# Main_oak_cm4_16.net
KiCad netlist of a schematic drawn in EAGLE
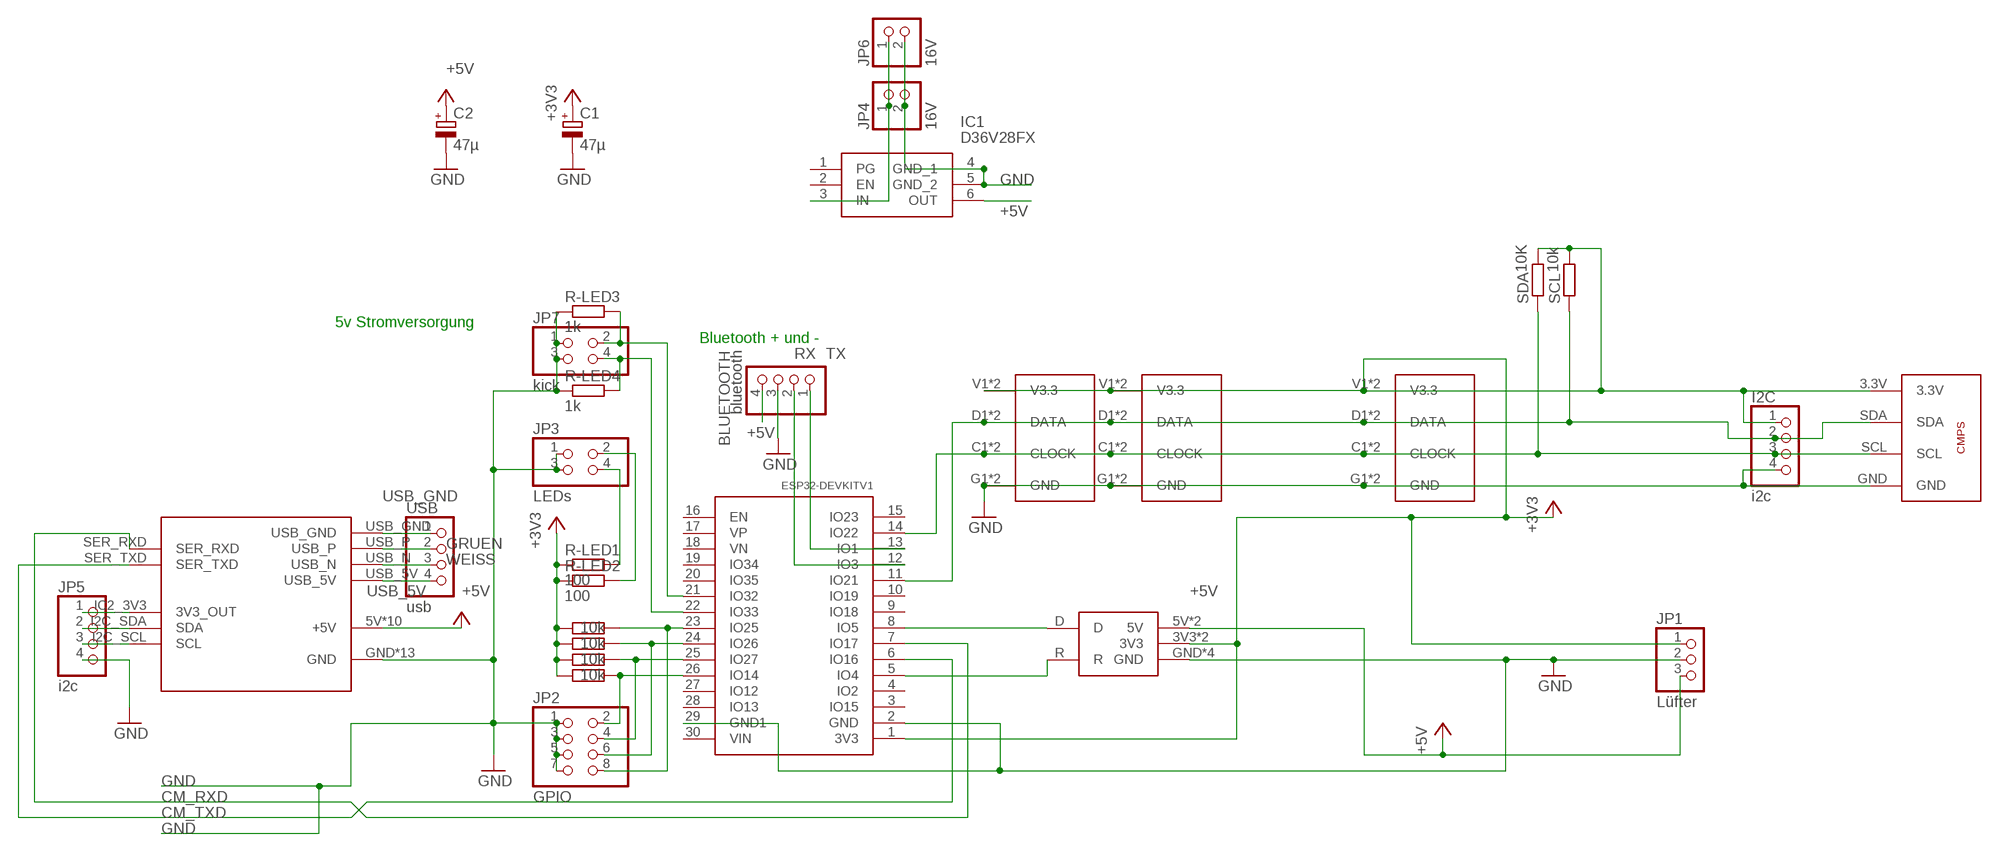
[diagram p0: schematic, sheet 1]

(export (version "E")
  (design (tool "Eeschema 10.0.6"))
  (components
    (comp (ref "BLUETOOTH")
      (value "bluetooth")
      (footprint "eagle-import:1X04")
      (libsource (lib "eagle-import") (part "PINHD-1X4"))
    )
    (comp (ref "C1")
      (value "47µ")
      (footprint "eagle-import:E2,5-6E")
      (libsource (lib "eagle-import") (part "CPOL-EUE2,5-6E"))
    )
    (comp (ref "C2")
      (value "47µ")
      (footprint "eagle-import:E2,5-6E")
      (libsource (lib "eagle-import") (part "CPOL-EUE2,5-6E"))
    )
    (comp (ref "I2C")
      (value "i2c")
      (footprint "eagle-import:1X04")
      (libsource (lib "eagle-import") (part "PINHD-1X4"))
    )
    (comp (ref "IC1")
      (value "D36V28FX")
      (footprint "eagle-import:D36V28FX")
      (libsource (lib "eagle-import") (part "D36V28FX"))
    )
    (comp (ref "JP1")
      (value "Lüfter")
      (footprint "eagle-import:1X03")
      (libsource (lib "eagle-import") (part "PINHD-1X3"))
    )
    (comp (ref "JP2")
      (value "GPIO")
      (footprint "eagle-import:2X04")
      (libsource (lib "eagle-import") (part "PINHD-2X4"))
    )
    (comp (ref "JP3")
      (value "LEDs")
      (footprint "eagle-import:2X02")
      (libsource (lib "eagle-import") (part "PINHD-2X2"))
    )
    (comp (ref "JP4")
      (value "16V")
      (footprint "eagle-import:1X02")
      (libsource (lib "eagle-import") (part "PINHD-1X2"))
    )
    (comp (ref "JP5")
      (value "i2c")
      (footprint "eagle-import:1X04")
      (libsource (lib "eagle-import") (part "PINHD-1X4"))
    )
    (comp (ref "JP6")
      (value "16V")
      (footprint "eagle-import:1X02")
      (libsource (lib "eagle-import") (part "PINHD-1X2"))
    )
    (comp (ref "JP7")
      (value "kick")
      (footprint "eagle-import:2X02")
      (libsource (lib "eagle-import") (part "PINHD-2X2"))
    )
    (comp (ref "R-LED1")
      (value "100")
      (footprint "eagle-import:0207_10")
      (libsource (lib "eagle-import") (part "R-EU_0207/10"))
    )
    (comp (ref "R-LED2")
      (value "100")
      (footprint "eagle-import:0207_10")
      (libsource (lib "eagle-import") (part "R-EU_0207/10"))
    )
    (comp (ref "R-LED3")
      (value "1k")
      (footprint "eagle-import:0207_10")
      (libsource (lib "eagle-import") (part "R-EU_0207/10"))
    )
    (comp (ref "R-LED4")
      (value "1k")
      (footprint "eagle-import:0207_10")
      (libsource (lib "eagle-import") (part "R-EU_0207/10"))
    )
    (comp (ref "R_AD14")
      (value "10k")
      (footprint "eagle-import:0207_10")
      (libsource (lib "eagle-import") (part "R-EU_0207/10"))
    )
    (comp (ref "R_AD25")
      (value "10k")
      (footprint "eagle-import:0207_10")
      (libsource (lib "eagle-import") (part "R-EU_0207/10"))
    )
    (comp (ref "R_AD26")
      (value "10k")
      (footprint "eagle-import:0207_10")
      (libsource (lib "eagle-import") (part "R-EU_0207/10"))
    )
    (comp (ref "R_AD27")
      (value "10k")
      (footprint "eagle-import:0207_10")
      (libsource (lib "eagle-import") (part "R-EU_0207/10"))
    )
    (comp (ref "SCL")
      (value "10k")
      (footprint "eagle-import:0207_10")
      (libsource (lib "eagle-import") (part "R-EU_0207/10"))
    )
    (comp (ref "SDA")
      (value "10K")
      (footprint "eagle-import:0207_10")
      (libsource (lib "eagle-import") (part "R-EU_0207/10"))
    )
    (comp (ref "U$1")
      (value "TASTER_LED")
      (footprint "eagle-import:TASTER_LED")
      (libsource (lib "eagle-import") (part "TASTER_LED"))
    )
    (comp (ref "U$3")
      (value "TASTER_LED")
      (footprint "eagle-import:TASTER_LED")
      (libsource (lib "eagle-import") (part "TASTER_LED"))
    )
    (comp (ref "U$5")
      (value "CM4-ADAPTER")
      (footprint "eagle-import:CM4-ADAPTER")
      (libsource (lib "eagle-import") (part "CM4-ADAPTER"))
    )
    (comp (ref "U$7")
      (value "TASTER_LED")
      (footprint "eagle-import:TASTER_LED")
      (libsource (lib "eagle-import") (part "TASTER_LED"))
    )
    (comp (ref "U$8")
      (value "CMPS")
      (footprint "eagle-import:CMPS")
      (libsource (lib "eagle-import") (part "CMPS"))
    )
    (comp (ref "U$11")
      (value "CANBUS")
      (footprint "eagle-import:CANBUS")
      (libsource (lib "eagle-import") (part "CANBUS"))
    )
    (comp (ref "U$13")
      (value "ESP32DEVKITV1")
      (footprint "eagle-import:ESP32-DEVKITV1")
      (libsource (lib "eagle-import") (part "ESP32DEVKITV1"))
    )
    (comp (ref "USB")
      (value "usb")
      (footprint "eagle-import:1X04")
      (libsource (lib "eagle-import") (part "PINHD-1X4"))
    )
  )
  (nets
    (net (code "1") (name "+3V3") (class "Default")
      (node (ref "C1") (pin "+") (pinfunction "+_+") (pintype "passive"))
      (node (ref "I2C") (pin "1") (pinfunction "1_1") (pintype "passive"))
      (node (ref "JP1") (pin "1") (pinfunction "1_1") (pintype "passive"))
      (node (ref "R-LED1") (pin "1") (pinfunction "1_1") (pintype "passive"))
      (node (ref "R-LED2") (pin "1") (pinfunction "1_1") (pintype "passive"))
      (node (ref "R_AD14") (pin "1") (pinfunction "1_1") (pintype "passive"))
      (node (ref "R_AD25") (pin "1") (pinfunction "1_1") (pintype "passive"))
      (node (ref "R_AD26") (pin "1") (pinfunction "1_1") (pintype "passive"))
      (node (ref "R_AD27") (pin "1") (pinfunction "1_1") (pintype "passive"))
      (node (ref "SCL") (pin "2") (pinfunction "2_2") (pintype "passive"))
      (node (ref "SDA") (pin "2") (pinfunction "2_2") (pintype "passive"))
      (node (ref "U$1") (pin "V1") (pinfunction "V3.3_V1") (pintype "bidirectional"))
      (node (ref "U$1") (pin "V2") (pinfunction "V3.3_V2") (pintype "bidirectional"))
      (node (ref "U$11") (pin "3V3") (pinfunction "3V3_3V3") (pintype "bidirectional"))
      (node (ref "U$11") (pin "3V3_1") (pinfunction "3V3_3V3_1") (pintype "bidirectional"))
      (node (ref "U$13") (pin "1") (pinfunction "3V3_1") (pintype "bidirectional"))
      (node (ref "U$3") (pin "V1") (pinfunction "V3.3_V1") (pintype "bidirectional"))
      (node (ref "U$3") (pin "V2") (pinfunction "V3.3_V2") (pintype "bidirectional"))
      (node (ref "U$7") (pin "V1") (pinfunction "V3.3_V1") (pintype "bidirectional"))
      (node (ref "U$7") (pin "V2") (pinfunction "V3.3_V2") (pintype "bidirectional"))
      (node (ref "U$8") (pin "3.3V") (pinfunction "3.3V_3.3V") (pintype "bidirectional"))
    )
    (net (code "2") (name "+5V") (class "Default")
      (node (ref "BLUETOOTH") (pin "4") (pinfunction "4_4") (pintype "passive"))
      (node (ref "C2") (pin "+") (pinfunction "+_+") (pintype "passive"))
      (node (ref "IC1") (pin "6") (pinfunction "OUT_6") (pintype "bidirectional"))
      (node (ref "JP1") (pin "3") (pinfunction "3_3") (pintype "passive"))
      (node (ref "U$11") (pin "5V") (pinfunction "5V_5V") (pintype "bidirectional"))
      (node (ref "U$11") (pin "5V_1") (pinfunction "5V_5V_1") (pintype "bidirectional"))
      (node (ref "U$5") (pin "5V") (pinfunction "+5V_5V") (pintype "bidirectional"))
      (node (ref "U$5") (pin "5V.1") (pinfunction "+5V_5V.1") (pintype "bidirectional"))
      (node (ref "U$5") (pin "5V.2") (pinfunction "+5V_5V.2") (pintype "bidirectional"))
      (node (ref "U$5") (pin "5V.3") (pinfunction "+5V_5V.3") (pintype "bidirectional"))
      (node (ref "U$5") (pin "5V.4") (pinfunction "+5V_5V.4") (pintype "bidirectional"))
      (node (ref "U$5") (pin "5V.5") (pinfunction "+5V_5V.5") (pintype "bidirectional"))
      (node (ref "U$5") (pin "5V.6") (pinfunction "+5V_5V.6") (pintype "bidirectional"))
      (node (ref "U$5") (pin "5V.7") (pinfunction "+5V_5V.7") (pintype "bidirectional"))
      (node (ref "U$5") (pin "5V.8") (pinfunction "+5V_5V.8") (pintype "bidirectional"))
      (node (ref "U$5") (pin "5V.9") (pinfunction "+5V_5V.9") (pintype "bidirectional"))
    )
    (net (code "3") (name "/CM_RXD") (class "Default")
      (node (ref "U$13") (pin "7") (pinfunction "IO17_7") (pintype "bidirectional"))
      (node (ref "U$5") (pin "SER_RXD") (pinfunction "SER_RXD_SER_RXD") (pintype "bidirectional"))
    )
    (net (code "4") (name "/CM_TXD") (class "Default")
      (node (ref "U$13") (pin "6") (pinfunction "IO16_6") (pintype "bidirectional"))
      (node (ref "U$5") (pin "SER_TXD") (pinfunction "SER_TXD_SER_TXD") (pintype "bidirectional"))
    )
    (net (code "5") (name "/GRUEN") (class "Default")
      (node (ref "U$5") (pin "USB_P") (pinfunction "USB_P_USB_P") (pintype "bidirectional"))
      (node (ref "USB") (pin "2") (pinfunction "2_2") (pintype "passive"))
    )
    (net (code "6") (name "/RX") (class "Default")
      (node (ref "BLUETOOTH") (pin "2") (pinfunction "2_2") (pintype "passive"))
      (node (ref "U$13") (pin "12") (pinfunction "IO3_12") (pintype "bidirectional"))
    )
    (net (code "7") (name "/TX") (class "Default")
      (node (ref "BLUETOOTH") (pin "1") (pinfunction "1_1") (pintype "passive"))
      (node (ref "U$13") (pin "13") (pinfunction "IO1_13") (pintype "bidirectional"))
    )
    (net (code "8") (name "/USB_5V") (class "Default")
      (node (ref "U$5") (pin "USB_5V") (pinfunction "USB_5V_USB_5V") (pintype "bidirectional"))
      (node (ref "USB") (pin "4") (pinfunction "4_4") (pintype "passive"))
    )
    (net (code "9") (name "/USB_GND") (class "Default")
      (node (ref "U$5") (pin "USB_GND") (pinfunction "USB_GND_USB_GND") (pintype "bidirectional"))
      (node (ref "USB") (pin "1") (pinfunction "1_1") (pintype "passive"))
    )
    (net (code "10") (name "/WEISS") (class "Default")
      (node (ref "U$5") (pin "USB_N") (pinfunction "USB_N_USB_N") (pintype "bidirectional"))
      (node (ref "USB") (pin "3") (pinfunction "3_3") (pintype "passive"))
    )
    (net (code "11") (name "GND") (class "Default")
      (node (ref "BLUETOOTH") (pin "3") (pinfunction "3_3") (pintype "passive"))
      (node (ref "C1") (pin "-") (pinfunction "-_-") (pintype "passive"))
      (node (ref "C2") (pin "-") (pinfunction "-_-") (pintype "passive"))
      (node (ref "I2C") (pin "4") (pinfunction "4_4") (pintype "passive"))
      (node (ref "IC1") (pin "4") (pinfunction "GND_1_4") (pintype "bidirectional"))
      (node (ref "IC1") (pin "5") (pinfunction "GND_2_5") (pintype "bidirectional"))
      (node (ref "JP1") (pin "2") (pinfunction "2_2") (pintype "passive"))
      (node (ref "JP2") (pin "1") (pinfunction "1_1") (pintype "passive"))
      (node (ref "JP2") (pin "3") (pinfunction "3_3") (pintype "passive"))
      (node (ref "JP2") (pin "5") (pinfunction "5_5") (pintype "passive"))
      (node (ref "JP2") (pin "7") (pinfunction "7_7") (pintype "passive"))
      (node (ref "JP3") (pin "1") (pinfunction "1_1") (pintype "passive"))
      (node (ref "JP3") (pin "3") (pinfunction "3_3") (pintype "passive"))
      (node (ref "JP4") (pin "2") (pinfunction "2_2") (pintype "passive"))
      (node (ref "JP5") (pin "4") (pinfunction "4_4") (pintype "passive"))
      (node (ref "JP6") (pin "2") (pinfunction "2_2") (pintype "passive"))
      (node (ref "JP7") (pin "1") (pinfunction "1_1") (pintype "passive"))
      (node (ref "JP7") (pin "3") (pinfunction "3_3") (pintype "passive"))
      (node (ref "R-LED3") (pin "1") (pinfunction "1_1") (pintype "passive"))
      (node (ref "R-LED4") (pin "1") (pinfunction "1_1") (pintype "passive"))
      (node (ref "U$1") (pin "G1") (pinfunction "GND_G1") (pintype "bidirectional"))
      (node (ref "U$1") (pin "G2") (pinfunction "GND_G2") (pintype "bidirectional"))
      (node (ref "U$11") (pin "GND") (pinfunction "GND_GND") (pintype "bidirectional"))
      (node (ref "U$11") (pin "GND_1") (pinfunction "GND_GND_1") (pintype "bidirectional"))
      (node (ref "U$11") (pin "GND_2") (pinfunction "GND_GND_2") (pintype "bidirectional"))
      (node (ref "U$11") (pin "GND_3") (pinfunction "GND_GND_3") (pintype "bidirectional"))
      (node (ref "U$13") (pin "2") (pinfunction "GND_2") (pintype "bidirectional"))
      (node (ref "U$13") (pin "29") (pinfunction "GND1_29") (pintype "bidirectional"))
      (node (ref "U$3") (pin "G1") (pinfunction "GND_G1") (pintype "bidirectional"))
      (node (ref "U$3") (pin "G2") (pinfunction "GND_G2") (pintype "bidirectional"))
      (node (ref "U$5") (pin "GND") (pinfunction "GND_GND") (pintype "bidirectional"))
      (node (ref "U$5") (pin "GND1") (pinfunction "GND_GND1") (pintype "bidirectional"))
      (node (ref "U$5") (pin "GND2") (pinfunction "GND_GND2") (pintype "bidirectional"))
      (node (ref "U$5") (pin "GND3") (pinfunction "GND_GND3") (pintype "bidirectional"))
      (node (ref "U$5") (pin "GND4") (pinfunction "GND_GND4") (pintype "bidirectional"))
      (node (ref "U$5") (pin "GND5") (pinfunction "GND_GND5") (pintype "bidirectional"))
      (node (ref "U$5") (pin "GND6") (pinfunction "GND_GND6") (pintype "bidirectional"))
      (node (ref "U$5") (pin "GND7") (pinfunction "GND_GND7") (pintype "bidirectional"))
      (node (ref "U$5") (pin "GND8") (pinfunction "GND_GND8") (pintype "bidirectional"))
      (node (ref "U$5") (pin "GND9") (pinfunction "GND_GND9") (pintype "bidirectional"))
      (node (ref "U$5") (pin "I2C_GND") (pinfunction "GND_I2C_GND") (pintype "bidirectional"))
      (node (ref "U$5") (pin "SER_GND") (pinfunction "GND_SER_GND") (pintype "bidirectional"))
      (node (ref "U$5") (pin "SER_GND2") (pinfunction "GND_SER_GND2") (pintype "bidirectional"))
      (node (ref "U$7") (pin "G1") (pinfunction "GND_G1") (pintype "bidirectional"))
      (node (ref "U$7") (pin "G2") (pinfunction "GND_G2") (pintype "bidirectional"))
      (node (ref "U$8") (pin "GND") (pinfunction "GND_GND") (pintype "bidirectional"))
    )
    (net (code "12") (name "Net-(IC1-IN)") (class "Default")
      (node (ref "IC1") (pin "3") (pinfunction "IN_3") (pintype "bidirectional"))
      (node (ref "JP4") (pin "1") (pinfunction "1_1") (pintype "passive"))
      (node (ref "JP6") (pin "1") (pinfunction "1_1") (pintype "passive"))
    )
    (net (code "13") (name "Net-(JP3-Pad2)") (class "Default")
      (node (ref "JP3") (pin "2") (pinfunction "2_2") (pintype "passive"))
      (node (ref "R-LED2") (pin "2") (pinfunction "2_2") (pintype "passive"))
    )
    (net (code "14") (name "Net-(JP3-Pad4)") (class "Default")
      (node (ref "JP3") (pin "4") (pinfunction "4_4") (pintype "passive"))
      (node (ref "R-LED1") (pin "2") (pinfunction "2_2") (pintype "passive"))
    )
    (net (code "15") (name "Net-(U$5-3V3_OUT)") (class "Default")
      (node (ref "JP5") (pin "1") (pinfunction "1_1") (pintype "passive"))
      (node (ref "U$5") (pin "IC2_3V3") (pinfunction "3V3_OUT_IC2_3V3") (pintype "bidirectional"))
    )
    (net (code "16") (name "Net-(U$5-SCL)") (class "Default")
      (node (ref "JP5") (pin "3") (pinfunction "3_3") (pintype "passive"))
      (node (ref "U$5") (pin "I2C_SCL") (pinfunction "SCL_I2C_SCL") (pintype "bidirectional"))
    )
    (net (code "17") (name "Net-(U$5-SDA)") (class "Default")
      (node (ref "JP5") (pin "2") (pinfunction "2_2") (pintype "passive"))
      (node (ref "U$5") (pin "I2C_SDA") (pinfunction "SDA_I2C_SDA") (pintype "bidirectional"))
    )
    (net (code "18") (name "Net-(U$13-IO4)") (class "Default")
      (node (ref "U$11") (pin "R") (pinfunction "R_R") (pintype "bidirectional"))
      (node (ref "U$13") (pin "5") (pinfunction "IO4_5") (pintype "bidirectional"))
    )
    (net (code "19") (name "Net-(U$13-IO5)") (class "Default")
      (node (ref "U$11") (pin "D") (pinfunction "D_D") (pintype "bidirectional"))
      (node (ref "U$13") (pin "8") (pinfunction "IO5_8") (pintype "bidirectional"))
    )
    (net (code "20") (name "Net-(U$13-IO14)") (class "Default")
      (node (ref "JP2") (pin "2") (pinfunction "2_2") (pintype "passive"))
      (node (ref "R_AD14") (pin "2") (pinfunction "2_2") (pintype "passive"))
      (node (ref "U$13") (pin "26") (pinfunction "IO14_26") (pintype "bidirectional"))
    )
    (net (code "21") (name "Net-(U$13-IO21)") (class "Default")
      (node (ref "I2C") (pin "2") (pinfunction "2_2") (pintype "passive"))
      (node (ref "SCL") (pin "1") (pinfunction "1_1") (pintype "passive"))
      (node (ref "U$1") (pin "D1") (pinfunction "DATA_D1") (pintype "bidirectional"))
      (node (ref "U$1") (pin "D2") (pinfunction "DATA_D2") (pintype "bidirectional"))
      (node (ref "U$13") (pin "11") (pinfunction "IO21_11") (pintype "bidirectional"))
      (node (ref "U$3") (pin "D1") (pinfunction "DATA_D1") (pintype "bidirectional"))
      (node (ref "U$3") (pin "D2") (pinfunction "DATA_D2") (pintype "bidirectional"))
      (node (ref "U$7") (pin "D1") (pinfunction "DATA_D1") (pintype "bidirectional"))
      (node (ref "U$7") (pin "D2") (pinfunction "DATA_D2") (pintype "bidirectional"))
      (node (ref "U$8") (pin "SDA") (pinfunction "SDA_SDA") (pintype "bidirectional"))
    )
    (net (code "22") (name "Net-(U$13-IO22)") (class "Default")
      (node (ref "I2C") (pin "3") (pinfunction "3_3") (pintype "passive"))
      (node (ref "SDA") (pin "1") (pinfunction "1_1") (pintype "passive"))
      (node (ref "U$1") (pin "C1") (pinfunction "CLOCK_C1") (pintype "bidirectional"))
      (node (ref "U$1") (pin "C2") (pinfunction "CLOCK_C2") (pintype "bidirectional"))
      (node (ref "U$13") (pin "14") (pinfunction "IO22_14") (pintype "bidirectional"))
      (node (ref "U$3") (pin "C1") (pinfunction "CLOCK_C1") (pintype "bidirectional"))
      (node (ref "U$3") (pin "C2") (pinfunction "CLOCK_C2") (pintype "bidirectional"))
      (node (ref "U$7") (pin "C1") (pinfunction "CLOCK_C1") (pintype "bidirectional"))
      (node (ref "U$7") (pin "C2") (pinfunction "CLOCK_C2") (pintype "bidirectional"))
      (node (ref "U$8") (pin "SCL") (pinfunction "SCL_SCL") (pintype "bidirectional"))
    )
    (net (code "23") (name "Net-(U$13-IO25)") (class "Default")
      (node (ref "JP2") (pin "8") (pinfunction "8_8") (pintype "passive"))
      (node (ref "R_AD25") (pin "2") (pinfunction "2_2") (pintype "passive"))
      (node (ref "U$13") (pin "23") (pinfunction "IO25_23") (pintype "bidirectional"))
    )
    (net (code "24") (name "Net-(U$13-IO26)") (class "Default")
      (node (ref "JP2") (pin "6") (pinfunction "6_6") (pintype "passive"))
      (node (ref "R_AD26") (pin "2") (pinfunction "2_2") (pintype "passive"))
      (node (ref "U$13") (pin "24") (pinfunction "IO26_24") (pintype "bidirectional"))
    )
    (net (code "25") (name "Net-(U$13-IO27)") (class "Default")
      (node (ref "JP2") (pin "4") (pinfunction "4_4") (pintype "passive"))
      (node (ref "R_AD27") (pin "2") (pinfunction "2_2") (pintype "passive"))
      (node (ref "U$13") (pin "25") (pinfunction "IO27_25") (pintype "bidirectional"))
    )
    (net (code "26") (name "Net-(U$13-IO32)") (class "Default")
      (node (ref "JP7") (pin "2") (pinfunction "2_2") (pintype "passive"))
      (node (ref "R-LED3") (pin "2") (pinfunction "2_2") (pintype "passive"))
      (node (ref "U$13") (pin "21") (pinfunction "IO32_21") (pintype "bidirectional"))
    )
    (net (code "27") (name "Net-(U$13-IO33)") (class "Default")
      (node (ref "JP7") (pin "4") (pinfunction "4_4") (pintype "passive"))
      (node (ref "R-LED4") (pin "2") (pinfunction "2_2") (pintype "passive"))
      (node (ref "U$13") (pin "22") (pinfunction "IO33_22") (pintype "bidirectional"))
    )
    (net (code "28") (name "unconnected-(IC1-EN-Pad2)") (class "Default")
      (node (ref "IC1") (pin "2") (pinfunction "EN_2") (pintype "bidirectional"))
    )
    (net (code "29") (name "unconnected-(IC1-PG-Pad1)") (class "Default")
      (node (ref "IC1") (pin "1") (pinfunction "PG_1") (pintype "bidirectional"))
    )
    (net (code "30") (name "unconnected-(U$13-EN-Pad16)") (class "Default")
      (node (ref "U$13") (pin "16") (pinfunction "EN_16") (pintype "bidirectional"))
    )
    (net (code "31") (name "unconnected-(U$13-IO2-Pad4)") (class "Default")
      (node (ref "U$13") (pin "4") (pinfunction "IO2_4") (pintype "bidirectional"))
    )
    (net (code "32") (name "unconnected-(U$13-IO12-Pad27)") (class "Default")
      (node (ref "U$13") (pin "27") (pinfunction "IO12_27") (pintype "bidirectional"))
    )
    (net (code "33") (name "unconnected-(U$13-IO13-Pad28)") (class "Default")
      (node (ref "U$13") (pin "28") (pinfunction "IO13_28") (pintype "bidirectional"))
    )
    (net (code "34") (name "unconnected-(U$13-IO15-Pad3)") (class "Default")
      (node (ref "U$13") (pin "3") (pinfunction "IO15_3") (pintype "bidirectional"))
    )
    (net (code "35") (name "unconnected-(U$13-IO18-Pad9)") (class "Default")
      (node (ref "U$13") (pin "9") (pinfunction "IO18_9") (pintype "bidirectional"))
    )
    (net (code "36") (name "unconnected-(U$13-IO19-Pad10)") (class "Default")
      (node (ref "U$13") (pin "10") (pinfunction "IO19_10") (pintype "bidirectional"))
    )
    (net (code "37") (name "unconnected-(U$13-IO23-Pad15)") (class "Default")
      (node (ref "U$13") (pin "15") (pinfunction "IO23_15") (pintype "bidirectional"))
    )
    (net (code "38") (name "unconnected-(U$13-IO34-Pad19)") (class "Default")
      (node (ref "U$13") (pin "19") (pinfunction "IO34_19") (pintype "bidirectional"))
    )
    (net (code "39") (name "unconnected-(U$13-IO35-Pad20)") (class "Default")
      (node (ref "U$13") (pin "20") (pinfunction "IO35_20") (pintype "bidirectional"))
    )
    (net (code "40") (name "unconnected-(U$13-VIN-Pad30)") (class "Default")
      (node (ref "U$13") (pin "30") (pinfunction "VIN_30") (pintype "bidirectional"))
    )
    (net (code "41") (name "unconnected-(U$13-VN-Pad18)") (class "Default")
      (node (ref "U$13") (pin "18") (pinfunction "VN_18") (pintype "bidirectional"))
    )
    (net (code "42") (name "unconnected-(U$13-VP-Pad17)") (class "Default")
      (node (ref "U$13") (pin "17") (pinfunction "VP_17") (pintype "bidirectional"))
    )
  )
)
